# MODULO_BUZZER.net
KiCad netlist of a schematic drawn in EAGLE
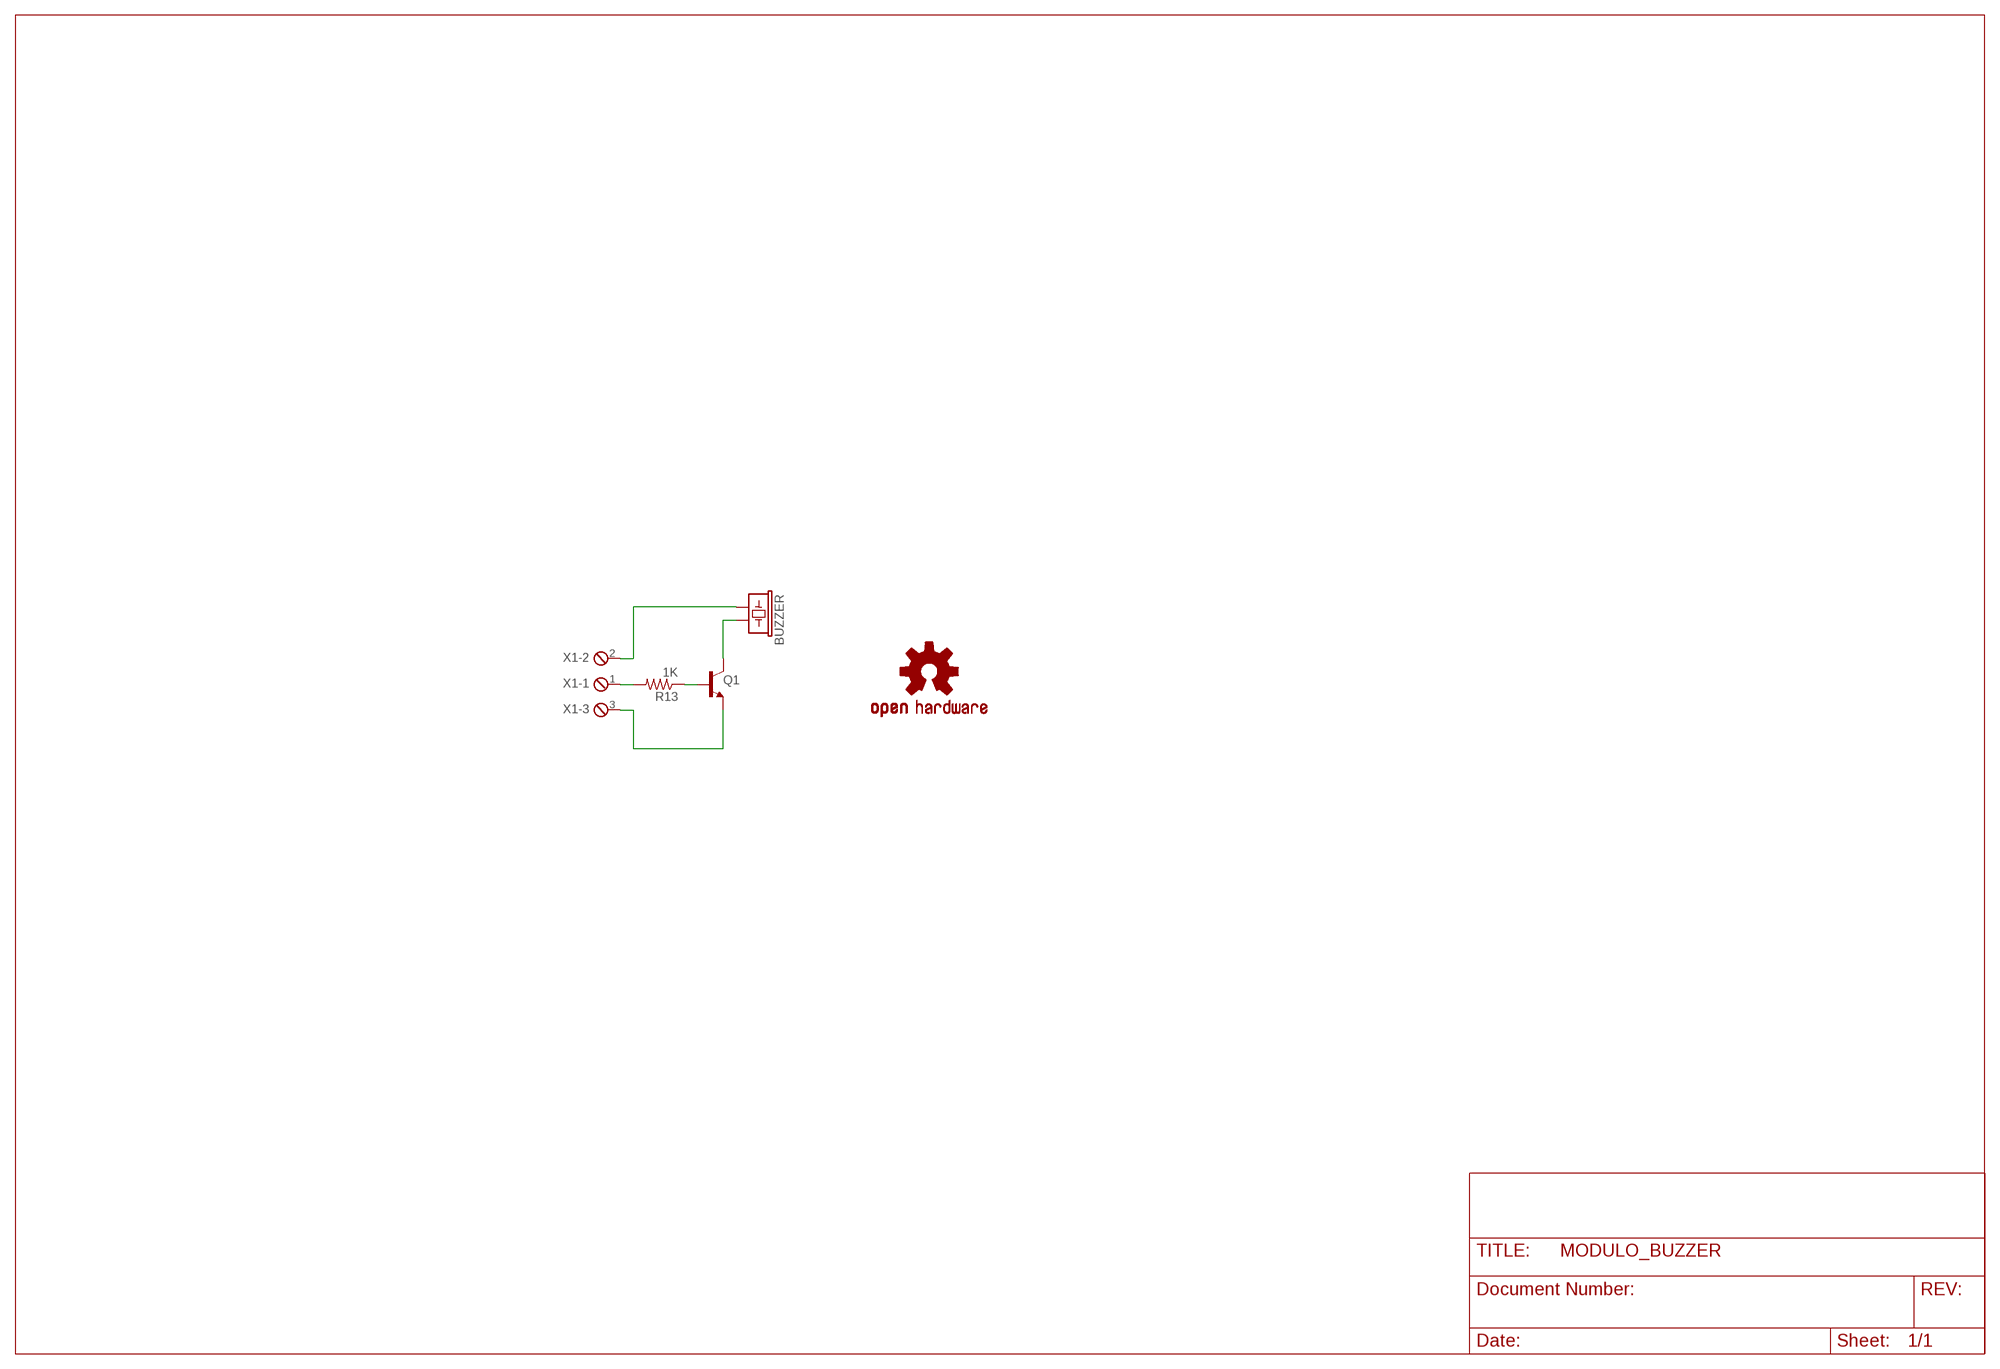
[diagram p0: schematic, sheet 1]

(export (version "E")
  (design (tool "Eeschema 10.0.6"))
  (components
    (comp (ref "BUZZER")
      (value "BUZZERNS")
      (footprint "eagle-import:BUZZER-12MM-NS")
      (libsource (lib "eagle-import") (part "BUZZERNS"))
    )
    (comp (ref "LOGO1")
      (value "OSHW-LOGOM")
      (footprint "eagle-import:OSHW-LOGO-M")
      (libsource (lib "eagle-import") (part "OSHW-LOGOM"))
    )
    (comp (ref "Q1")
      (value "BC548")
      (footprint "eagle-import:TO92-EBC")
      (libsource (lib "eagle-import") (part "BC548"))
    )
    (comp (ref "R13")
      (value "1K")
      (footprint "eagle-import:AXIAL-0.4")
      (libsource (lib "eagle-import") (part "RESISTORPTH-1/4W"))
    )
    (comp (ref "X1")
      (value "MPT3")
      (footprint "eagle-import:3POL254")
      (libsource (lib "eagle-import") (part "MPT3"))
    )
  )
  (nets
    (net (code "1") (name "Net-(BUZZER-1)") (class "Default")
      (node (ref "BUZZER") (pin "+") (pinfunction "1_+") (pintype "passive"))
      (node (ref "X1") (pin "2") (pinfunction "1_2") (pintype "passive"))
    )
    (net (code "2") (name "Net-(BUZZER-2)") (class "Default")
      (node (ref "BUZZER") (pin "-") (pinfunction "2_-") (pintype "passive"))
      (node (ref "Q1") (pin "C") (pinfunction "C_C") (pintype "passive"))
    )
    (net (code "3") (name "Net-(R13-1)") (class "Default")
      (node (ref "Q1") (pin "B") (pinfunction "B_B") (pintype "passive"))
      (node (ref "R13") (pin "P$1") (pinfunction "1_P$1") (pintype "passive"))
    )
    (net (code "4") (name "Net-(R13-2)") (class "Default")
      (node (ref "R13") (pin "P$2") (pinfunction "2_P$2") (pintype "passive"))
      (node (ref "X1") (pin "1") (pinfunction "1_1") (pintype "passive"))
    )
    (net (code "5") (name "Net-(X1C-1)") (class "Default")
      (node (ref "Q1") (pin "E") (pinfunction "E_E") (pintype "passive"))
      (node (ref "X1") (pin "3") (pinfunction "1_3") (pintype "passive"))
    )
  )
)
